# 24V_Sheet.net
KiCad netlist of a schematic drawn in Altium Designer
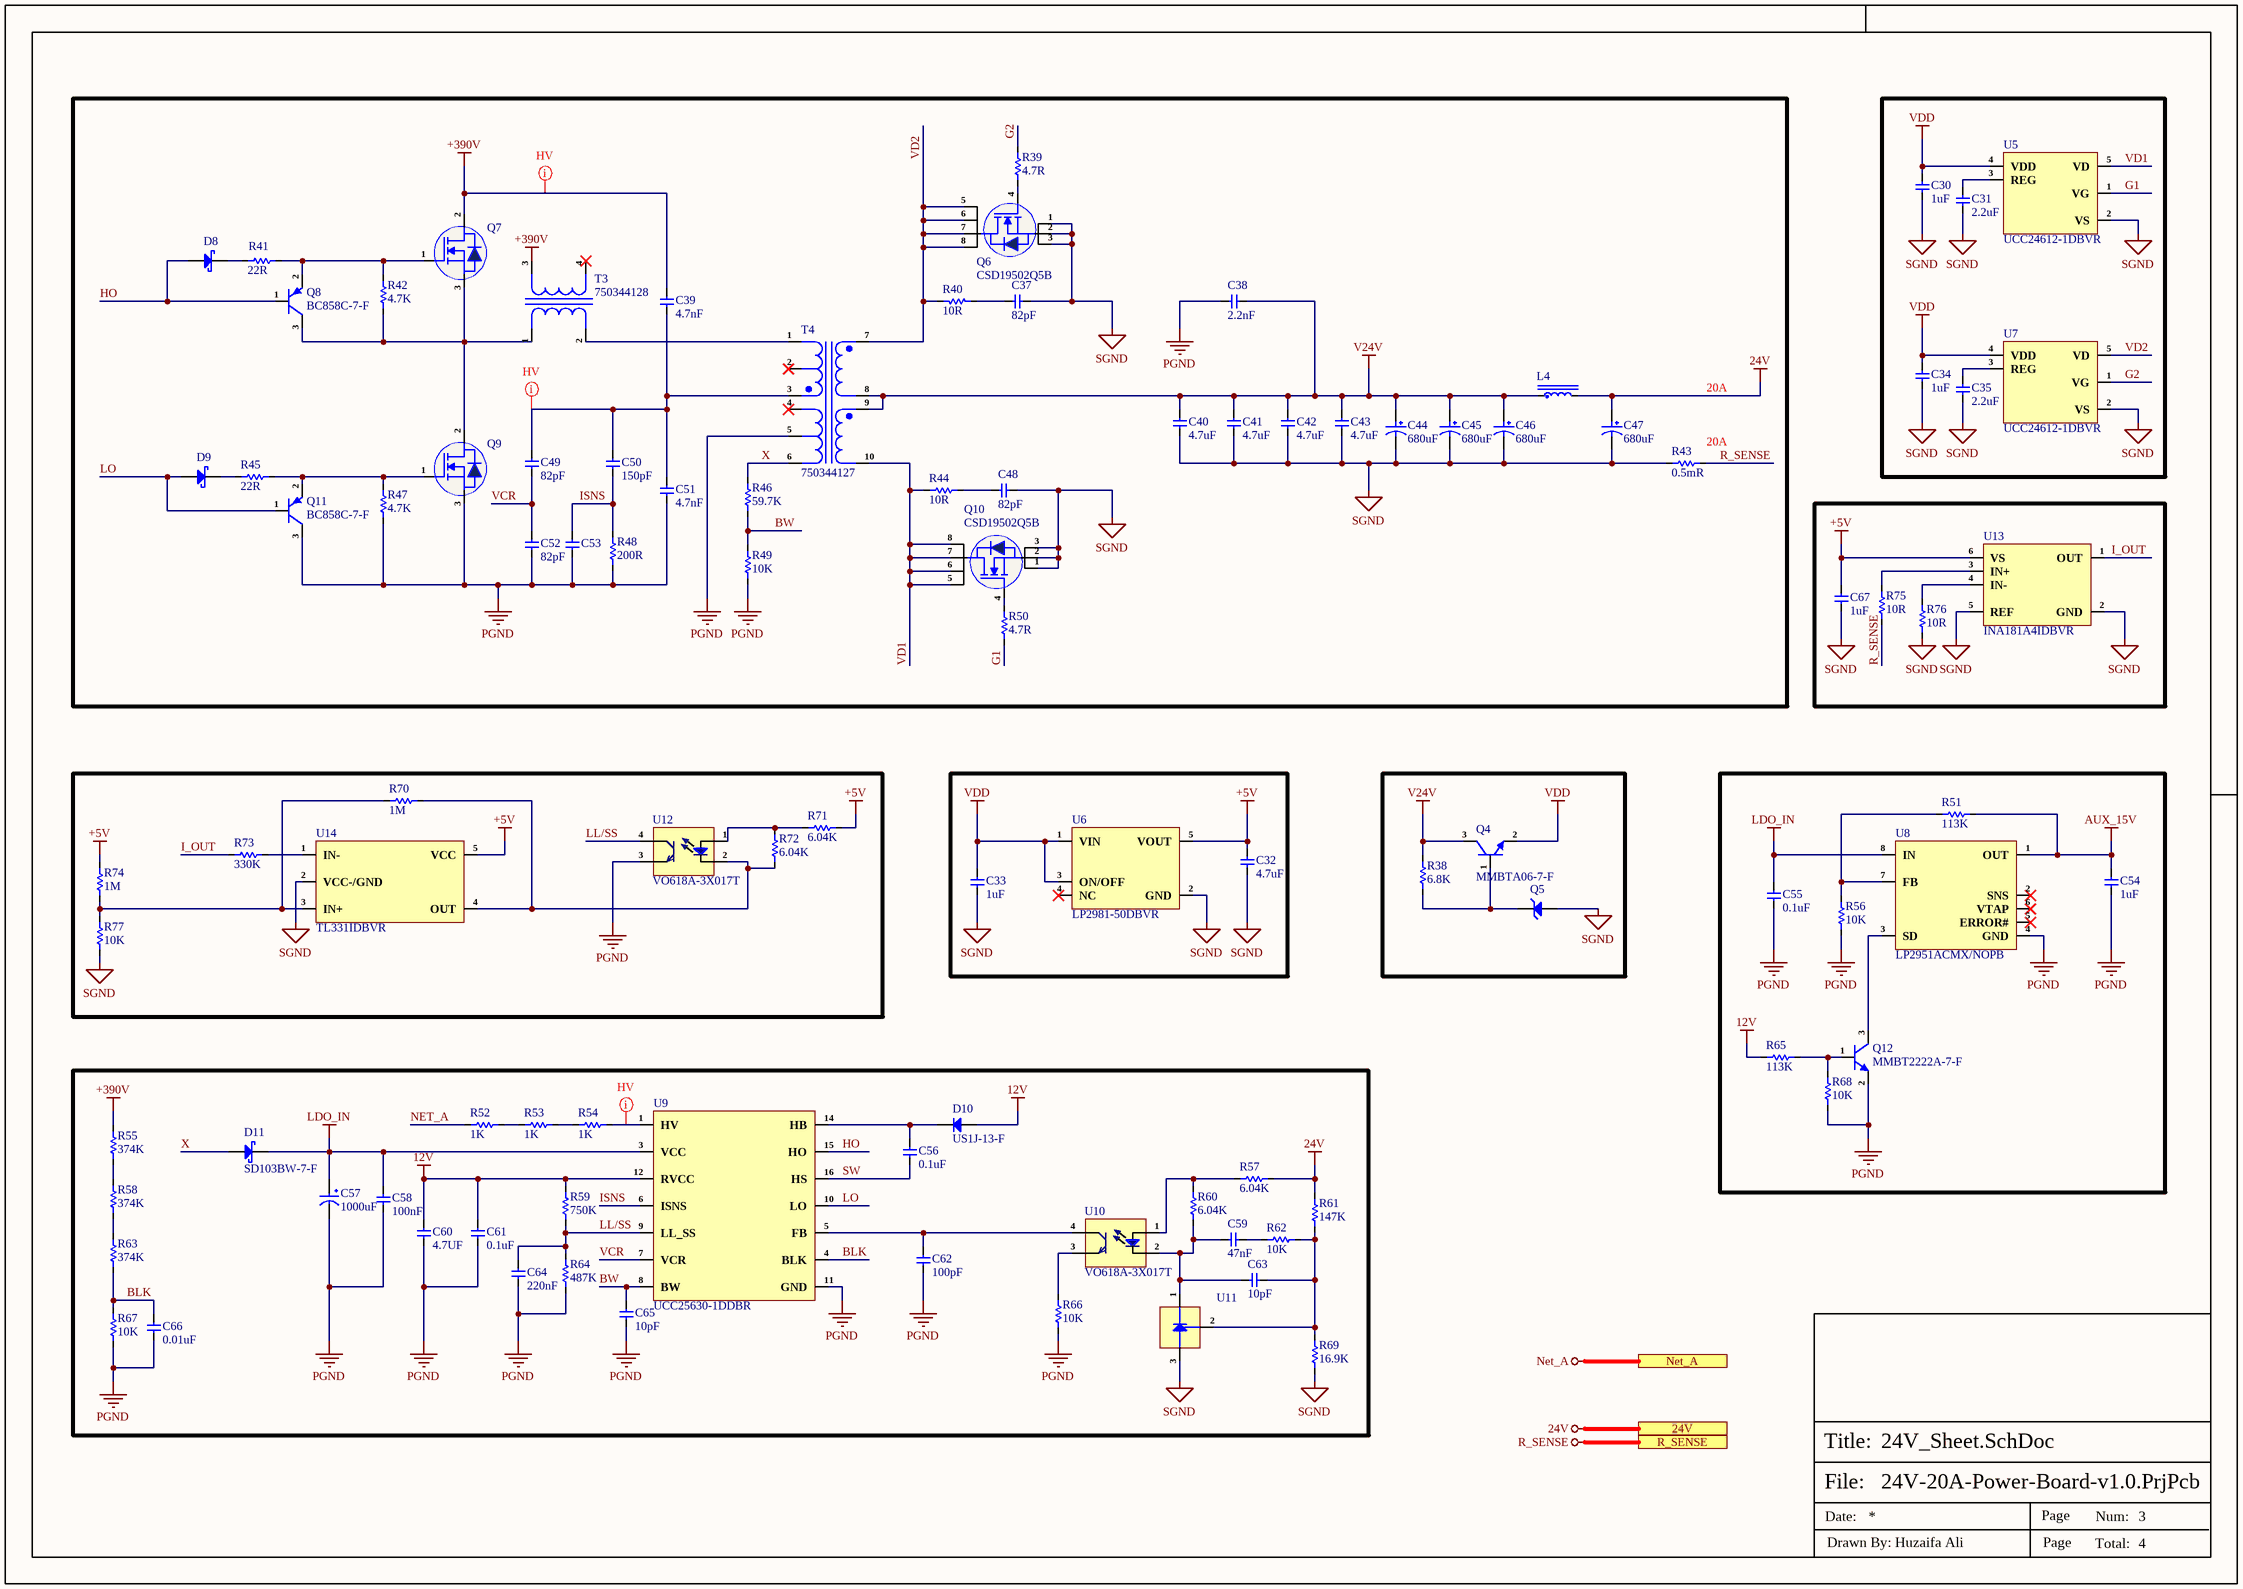
[diagram p0: 24V_Sheet.SchDoc]

(export (version "E")
  (design (tool "Eeschema 10.0.6"))
  (components
    (comp (ref "C30")
      (value "1uF")
      (footprint "Cap-0603")
      (description "1uF 25V X5R ±20% 0603 Multilayer Ceramic Capacitors MLCC - SMD/SMT ROHS")
      (fields (field (name "MANUFACTURER") "CCTC") (field (name "LCSC PART NUMBER") "C6266891"))
      (libsource (lib "eSpark Libraries") (part "TCC0603X5R105M250CT"))
    )
    (comp (ref "C31")
      (value "2.2uF")
      (footprint "Cap-0603")
      (description "CAP, 2.2µF, 35V, 10%, X5R, 0603")
      (fields
        (field (name "MANUFACTURER") "Murata")
        (field (name "MANUFACTURER PART NUMBER") "GRM188R6YA225KA12D")
      )
      (libsource (lib "eSpark Libraries") (part "GRM188R6YA225KA12D"))
    )
    (comp (ref "C32")
      (value "4.7uF")
      (footprint "Cap-0603")
      (description "CAP CER 4.7UF 16V X5R 0603")
      (fields
        (field (name "MANUFACTURER") "Yageo")
        (field (name "MANUFACTURER PART NUMBER") "CC0603KRX5R7BB475")
      )
      (libsource (lib "eSpark Libraries") (part "CC0603KRX5R7BB475"))
    )
    (comp (ref "C33")
      (value "1uF")
      (footprint "Cap-0603")
      (description "1uF 25V X5R ±20% 0603 Multilayer Ceramic Capacitors MLCC - SMD/SMT ROHS")
      (fields (field (name "MANUFACTURER") "CCTC") (field (name "LCSC PART NUMBER") "C6266891"))
      (libsource (lib "eSpark Libraries") (part "TCC0603X5R105M250CT"))
    )
    (comp (ref "C34")
      (value "1uF")
      (footprint "Cap-0603")
      (description "1uF 25V X5R ±20% 0603 Multilayer Ceramic Capacitors MLCC - SMD/SMT ROHS")
      (fields (field (name "MANUFACTURER") "CCTC") (field (name "LCSC PART NUMBER") "C6266891"))
      (libsource (lib "eSpark Libraries") (part "TCC0603X5R105M250CT"))
    )
    (comp (ref "C35")
      (value "2.2uF")
      (footprint "Cap-0603")
      (description "CAP, 2.2µF, 35V, 10%, X5R, 0603")
      (fields
        (field (name "MANUFACTURER") "Murata")
        (field (name "MANUFACTURER PART NUMBER") "GRM188R6YA225KA12D")
      )
      (libsource (lib "eSpark Libraries") (part "GRM188R6YA225KA12D"))
    )
    (comp (ref "C37")
      (value "82pF")
      (footprint "Cap-1206")
      (description "CAP CER 82PF 1KV U2J 1206")
      (fields (field (name "LCSC PART NUMBER") "C5125804") (field (name "MANUFACTURER") "Murata"))
      (libsource (lib "eSpark Libraries") (part "GCM31A7U3A820JX01D"))
    )
    (comp (ref "C38")
      (value "2.2nF")
      (footprint "KJKF222M2FF7035A075E")
      (description "2.2nF ±20% Y2 300V Plugin,P=7.5mm Safety Capacitors ROHS")
      (fields (field (name "LCSC PART NUMBER") "C2803195") (field (name "MANUFACTURER") "KNSCHA"))
      (libsource (lib "eSpark Libraries") (part "KJKF222M2FF7035A075E"))
    )
    (comp (ref "C39")
      (value "4.7nF")
      (footprint "MMK472J3AC2KN206G0")
      (description "4.7nF -40℃~+105℃ ±5% 1kV Plugin,P=10mm Polypropylene Film Capacitors (CBB) ROHS")
      (fields
        (field (name "MANUFACTURER") "KNSCHA")
        (field (name "MANUFACTURER PART NUMBER") "MMK472J3AC2KN206G0")
      )
      (libsource (lib "eSpark Libraries") (part "MMK472J3AC2KN206G0"))
    )
    (comp (ref "C40")
      (value "4.7uF")
      (footprint "Cap-1206")
      (description "CAP CER 4.7UF 100V X7S 1206")
      (fields
        (field (name "MANUFACTURER") "Murata")
        (field (name "MANUFACTURER PART NUMBER") "GRM31CC72A475KE11L")
      )
      (libsource (lib "eSpark Libraries") (part "GRM31CC72A475KE11L"))
    )
    (comp (ref "C41")
      (value "4.7uF")
      (footprint "Cap-1206")
      (description "CAP CER 4.7UF 100V X7S 1206")
      (fields
        (field (name "MANUFACTURER") "Murata")
        (field (name "MANUFACTURER PART NUMBER") "GRM31CC72A475KE11L")
      )
      (libsource (lib "eSpark Libraries") (part "GRM31CC72A475KE11L"))
    )
    (comp (ref "C42")
      (value "4.7uF")
      (footprint "Cap-1206")
      (description "CAP CER 4.7UF 100V X7S 1206")
      (fields
        (field (name "MANUFACTURER") "Murata")
        (field (name "MANUFACTURER PART NUMBER") "GRM31CC72A475KE11L")
      )
      (libsource (lib "eSpark Libraries") (part "GRM31CC72A475KE11L"))
    )
    (comp (ref "C43")
      (value "4.7uF")
      (footprint "Cap-1206")
      (description "CAP CER 4.7UF 100V X7S 1206")
      (fields
        (field (name "MANUFACTURER") "Murata")
        (field (name "MANUFACTURER PART NUMBER") "GRM31CC72A475KE11L")
      )
      (libsource (lib "eSpark Libraries") (part "GRM31CC72A475KE11L"))
    )
    (comp (ref "C44")
      (value "680uF")
      (footprint "ERS1HM681W20OT")
      (description "680uF 50V ±20% Plugin,D12.5xL20mm Aluminum Electrolytic Capacitors - Leaded ROHS")
      (fields
        (field (name "MANUFACTURER") "AISHI")
        (field (name "MANUFACTURER PART NUMBER") "ERS1HM681W20OT")
      )
      (libsource (lib "eSpark Libraries") (part "ERS1HM681W20OT"))
    )
    (comp (ref "C45")
      (value "680uF")
      (footprint "ERS1HM681W20OT")
      (description "680uF 50V ±20% Plugin,D12.5xL20mm Aluminum Electrolytic Capacitors - Leaded ROHS")
      (fields
        (field (name "MANUFACTURER") "AISHI")
        (field (name "MANUFACTURER PART NUMBER") "ERS1HM681W20OT")
      )
      (libsource (lib "eSpark Libraries") (part "ERS1HM681W20OT"))
    )
    (comp (ref "C46")
      (value "680uF")
      (footprint "ERS1HM681W20OT")
      (description "680uF 50V ±20% Plugin,D12.5xL20mm Aluminum Electrolytic Capacitors - Leaded ROHS")
      (fields
        (field (name "MANUFACTURER") "AISHI")
        (field (name "MANUFACTURER PART NUMBER") "ERS1HM681W20OT")
      )
      (libsource (lib "eSpark Libraries") (part "ERS1HM681W20OT"))
    )
    (comp (ref "C47")
      (value "680uF")
      (footprint "ERS1HM681W20OT")
      (description "680uF 50V ±20% Plugin,D12.5xL20mm Aluminum Electrolytic Capacitors - Leaded ROHS")
      (fields
        (field (name "MANUFACTURER") "AISHI")
        (field (name "MANUFACTURER PART NUMBER") "ERS1HM681W20OT")
      )
      (libsource (lib "eSpark Libraries") (part "ERS1HM681W20OT"))
    )
    (comp (ref "C48")
      (value "82pF")
      (footprint "Cap-1206")
      (description "CAP CER 82PF 1KV U2J 1206")
      (fields (field (name "LCSC PART NUMBER") "C5125804") (field (name "MANUFACTURER") "Murata"))
      (libsource (lib "eSpark Libraries") (part "GCM31A7U3A820JX01D"))
    )
    (comp (ref "C49")
      (value "82pF")
      (footprint "Cap-1206")
      (description "CAP CER 82PF 1KV U2J 1206")
      (fields (field (name "LCSC PART NUMBER") "C5125804") (field (name "MANUFACTURER") "Murata"))
      (libsource (lib "eSpark Libraries") (part "GCM31A7U3A820JX01D"))
    )
    (comp (ref "C50")
      (value "150pF")
      (footprint "Cap-1206")
      (description "CAP CER 150PF 1KV U2J 1206")
      (fields (field (name "LCSC PART NUMBER") "C162467") (field (name "MANUFACTURER") "Murata"))
      (libsource (lib "eSpark Libraries") (part "GRM31A7U3A151JW31D"))
    )
    (comp (ref "C51")
      (value "4.7nF")
      (footprint "MMK472J3AC2KN206G0")
      (description "4.7nF -40℃~+105℃ ±5% 1kV Plugin,P=10mm Polypropylene Film Capacitors (CBB) ROHS")
      (fields
        (field (name "MANUFACTURER") "KNSCHA")
        (field (name "MANUFACTURER PART NUMBER") "MMK472J3AC2KN206G0")
      )
      (libsource (lib "eSpark Libraries") (part "MMK472J3AC2KN206G0"))
    )
    (comp (ref "C52")
      (value "82pF")
      (footprint "Cap-1206")
      (description "CAP CER 82PF 1KV U2J 1206")
      (fields (field (name "LCSC PART NUMBER") "C5125804") (field (name "MANUFACTURER") "Murata"))
      (libsource (lib "eSpark Libraries") (part "GCM31A7U3A820JX01D"))
    )
    (comp (ref "C53")
      (value "RF15N3R3C500CT")
      (footprint "Cap-0402")
      (description "CAP CER 3.3PF 50V C0G/NP0 0402")
      (fields (field (name "MANUFACTURER") "Walsin Tech Corp") (field (name "LCSC PART NUMBER") "C172822"))
      (libsource (lib "eSpark Libraries") (part "RF15N3R3C500CT"))
    )
    (comp (ref "C54")
      (value "1uF")
      (footprint "Cap-0603")
      (description "1uF 25V X5R ±20% 0603 Multilayer Ceramic Capacitors MLCC - SMD/SMT ROHS")
      (fields (field (name "MANUFACTURER") "CCTC") (field (name "LCSC PART NUMBER") "C6266891"))
      (libsource (lib "eSpark Libraries") (part "TCC0603X5R105M250CT"))
    )
    (comp (ref "C55")
      (value "0.1uF")
      (footprint "Cap-1206")
      (description "50V 100nF C0G ±1% 1206 Multilayer Ceramic Capacitors MLCC - SMD/SMT ROHS")
      (fields (field (name "LCSC PART NUMBER") "C2981728") (field (name "MANUFACTURER") "Murata Electronics"))
      (libsource (lib "eSpark Libraries") (part "GRM31C5C1H104FA01L"))
    )
    (comp (ref "C56")
      (value "0.1uF")
      (footprint "Cap-0805")
      (description "CAP CER 0.1UF 100V X7R 0805")
      (fields (field (name "LCSC PART NUMBER") "C106243") (field (name "MANUFACTURER") "Yageo"))
      (libsource (lib "eSpark Libraries") (part "CC0805KKX7R0BB104"))
    )
    (comp (ref "C57")
      (value "1000uF")
      (footprint "VZH102M1HTR-1616")
      (description "1000uF 50V ±20% SMD,D16xL16.5mm Aluminum Electrolytic Capacitors - SMD ROHS")
      (fields (field (name "LCSC PART NUMBER") "C5266058") (field (name "MANUFACTURER") "Surge Components"))
      (libsource (lib "eSpark Libraries") (part "VZH102M1HTR-1616CS"))
    )
    (comp (ref "C58")
      (value "100nF")
      (footprint "Cap-0603")
      (description "CAP CER 0.1UF 50V X5R 0603")
      (fields
        (field (name "MANUFACTURER") "Yageo")
        (field (name "MANUFACTURER PART NUMBER") "CC0603KRX5R9BB104")
      )
      (libsource (lib "eSpark Libraries") (part "CC0603KRX5R9BB104"))
    )
    (comp (ref "C59")
      (value "47nF")
      (footprint "Cap-0402")
      (description "CAP CER 0.047UF 25V X7R 0402")
      (fields
        (field (name "MANUFACTURER") "Murata")
        (field (name "MANUFACTURER PART NUMBER") "GRM155R71E473KA88D")
      )
      (libsource (lib "eSpark Libraries") (part "GRM155R71E473KA88D"))
    )
    (comp (ref "C60")
      (value "4.7UF")
      (footprint "Cap-0603")
      (description "CAP CER 4.7UF 25V X5R 0603")
      (fields
        (field (name "MANUFACTURER") "Samsung")
        (field (name "MANUFACTURER PART NUMBER") "CL10A475KA8NQNC")
      )
      (libsource (lib "eSpark Libraries") (part "CL10A475KA8NQNC"))
    )
    (comp (ref "C61")
      (value "0.1uF")
      (footprint "Cap-0805")
      (description "CAP CER 0.1UF 100V X7R 0805")
      (fields (field (name "LCSC PART NUMBER") "C106243") (field (name "MANUFACTURER") "Yageo"))
      (libsource (lib "eSpark Libraries") (part "CC0805KKX7R0BB104"))
    )
    (comp (ref "C62")
      (value "100pF")
      (footprint "Cap-0603")
      (description "CAP CER 100PF 50V C0G/NPO 0603")
      (fields
        (field (name "MANUFACTURER") "Yageo")
        (field (name "MANUFACTURER PART NUMBER") "CC0603JRNPO9BN101")
      )
      (libsource (lib "eSpark Libraries") (part "CC0603JRNPO9BN101"))
    )
    (comp (ref "C63")
      (value "10pF")
      (footprint "Cap-0603")
      (description "CAP CER 10PF 50V C0G/NPO 0603")
      (fields
        (field (name "MANUFACTURER") "Yageo")
        (field (name "MANUFACTURER PART NUMBER") "CC0603JRNPO9BN100")
      )
      (libsource (lib "eSpark Libraries") (part "CC0603JRNPO9BN100"))
    )
    (comp (ref "C64")
      (value "220nF")
      (footprint "Cap-1206")
      (description "CAP CER 0.22UF 50V X7R 1206")
      (fields
        (field (name "MANUFACTURER") "Yageo")
        (field (name "MANUFACTURER PART NUMBER") "CC1206JKX7R9BB224")
      )
      (libsource (lib "eSpark Libraries") (part "CC1206JKX7R9BB224"))
    )
    (comp (ref "C65")
      (value "10pF")
      (footprint "Cap-0603")
      (description "CAP CER 10PF 50V C0G/NPO 0603")
      (fields
        (field (name "MANUFACTURER") "Yageo")
        (field (name "MANUFACTURER PART NUMBER") "CC0603JRNPO9BN100")
      )
      (libsource (lib "eSpark Libraries") (part "CC0603JRNPO9BN100"))
    )
    (comp (ref "C66")
      (value "0.01uF")
      (footprint "Cap-0805")
      (description "Multilayer Ceramic Capacitor, 0.01 uF, 50 V, ± 10%, X7R, 0805 [2012 Metric]")
      (fields
        (field (name "MANUFACTURER") "Yageo")
        (field (name "MANUFACTURER PART NUMBER") "CC0805KRX7R9BB103")
      )
      (libsource (lib "eSpark Libraries") (part "CC0805KRX7R9BB103"))
    )
    (comp (ref "C67")
      (value "1uF")
      (footprint "Cap-0603")
      (description "1uF 25V X5R ±20% 0603 Multilayer Ceramic Capacitors MLCC - SMD/SMT ROHS")
      (fields (field (name "MANUFACTURER") "CCTC") (field (name "LCSC PART NUMBER") "C6266891"))
      (libsource (lib "eSpark Libraries") (part "TCC0603X5R105M250CT"))
    )
    (comp (ref "D8")
      (value "SD103BW-7-F")
      (footprint "SOD-123")
      (description "DIODE SCHOTTKY 30V 350MA SOD123")
      (fields (field (name "LCSC PART NUMBER") "C151400") (field (name "MANUFACTURER") "Diodes"))
      (libsource (lib "eSpark Libraries") (part "SD103BW-7-F"))
    )
    (comp (ref "D9")
      (value "SD103BW-7-F")
      (footprint "SOD-123")
      (description "DIODE SCHOTTKY 30V 350MA SOD123")
      (fields (field (name "LCSC PART NUMBER") "C151400") (field (name "MANUFACTURER") "Diodes"))
      (libsource (lib "eSpark Libraries") (part "SD103BW-7-F"))
    )
    (comp (ref "D10")
      (value "US1J-13-F")
      (footprint "SMA")
      (description "DIODE GEN PURP 600V 1A SMA")
      (fields (field (name "LCSC PART NUMBER") "C85095") (field (name "MANUFACTURER") "Diodes"))
      (libsource (lib "eSpark Libraries") (part "US1J-13-F"))
    )
    (comp (ref "D11")
      (value "SD103BW-7-F")
      (footprint "SOD-123")
      (description "DIODE SCHOTTKY 30V 350MA SOD123")
      (fields (field (name "LCSC PART NUMBER") "C151400") (field (name "MANUFACTURER") "Diodes"))
      (libsource (lib "eSpark Libraries") (part "SD103BW-7-F"))
    )
    (comp (ref "L4")
      (value "PA2607.301NLT")
      (footprint "PA2607.301NLT")
      (description "FIXED IND 300NH 27A 0.29MOHM SMD")
      (fields (field (name "MANUFACTURER") "Pulse"))
      (libsource (lib "eSpark Libraries") (part "PA2607.301NLT"))
    )
    (comp (ref "Q4")
      (value "MMBTA06-7-F")
      (footprint "SOT-23")
      (description "TRANS NPN 80V 0.5A SOT23-3")
      (fields (field (name "MANUFACTURER") "Diodes"))
      (libsource (lib "eSpark Libraries") (part "MMBTA06-7-F"))
    )
    (comp (ref "Q5")
      (value "BZX384-C15,115")
      (footprint "SOD-323")
      (description "DIODE ZENER 15V 300MW SOD323")
      (fields (field (name "LCSC PART NUMBER") "C454989") (field (name "MANUFACTURER") "Nexperia"))
      (libsource (lib "eSpark Libraries") (part "BZX384-C15,115"))
    )
    (comp (ref "Q6")
      (value "CSD19502Q5B")
      (footprint "8-VSONP (5x6)")
      (description "MOSFET N-CH 80V 100A 8VSON")
      (fields (field (name "MANUFACTURER") "Texas Instruments") (field (name "LCSC PART NUMBER") "C2864118"))
      (libsource (lib "eSpark Libraries") (part "CSD19502Q5B"))
    )
    (comp (ref "Q7")
      (value "IPA60R120P7XKSA1")
      (footprint "TO-220-3")
      (description "MOSFET N-CH 600V 26A TO220")
      (fields (field (name "MANUFACTURER") "Infineon"))
      (libsource (lib "eSpark Libraries") (part "IPA60R120P7XKSA1"))
    )
    (comp (ref "Q8")
      (value "BC858C-7-F")
      (footprint "SOT-23")
      (description "TRANS PNP 30V 0.1A SOT23-3")
      (fields (field (name "LCSC PART NUMBER") "C526469") (field (name "MANUFACTURER") "Diodes"))
      (libsource (lib "eSpark Libraries") (part "BC858C-7-F"))
    )
    (comp (ref "Q9")
      (value "IPA60R120P7XKSA1")
      (footprint "TO-220-3")
      (description "MOSFET N-CH 600V 26A TO220")
      (fields (field (name "MANUFACTURER") "Infineon"))
      (libsource (lib "eSpark Libraries") (part "IPA60R120P7XKSA1"))
    )
    (comp (ref "Q10")
      (value "CSD19502Q5B")
      (footprint "8-VSONP (5x6)")
      (description "MOSFET N-CH 80V 100A 8VSON")
      (fields (field (name "MANUFACTURER") "Texas Instruments") (field (name "LCSC PART NUMBER") "C2864118"))
      (libsource (lib "eSpark Libraries") (part "CSD19502Q5B"))
    )
    (comp (ref "Q11")
      (value "BC858C-7-F")
      (footprint "SOT-23")
      (description "TRANS PNP 30V 0.1A SOT23-3")
      (fields (field (name "LCSC PART NUMBER") "C526469") (field (name "MANUFACTURER") "Diodes"))
      (libsource (lib "eSpark Libraries") (part "BC858C-7-F"))
    )
    (comp (ref "Q12")
      (value "MMBT2222A-7-F")
      (footprint "SOT-23")
      (description "TRANS NPN 40V 0.6A SMD SOT23-3")
      (fields (field (name "MANUFACTURER") "Diodes") (field (name "VOLTAGE") "40V"))
      (libsource (lib "eSpark Libraries") (part "MMBT2222A-7-F"))
    )
    (comp (ref "R38")
      (value "6.8K")
      (footprint "Res-0603")
      (description "RES SMD 6.8K OHM 0.1% 1/10W 0603")
      (fields
        (field (name "MANUFACTURER") "Yageo")
        (field (name "MANUFACTURER PART NUMBER") "RT0603BRE076K8L")
      )
      (libsource (lib "eSpark Libraries") (part "RT0603BRE076K8L"))
    )
    (comp (ref "R39")
      (value "4.7R")
      (footprint "Res-0603")
      (description "RES 4.7 OHM 1% 1/10W 0603")
      (fields
        (field (name "MANUFACTURER") "Yageo")
        (field (name "MANUFACTURER PART NUMBER") "RC0603FR-074R7L")
      )
      (libsource (lib "eSpark Libraries") (part "RC0603FR-074R7L"))
    )
    (comp (ref "R40")
      (value "10R")
      (footprint "RES-0805")
      (description "RES SMD 10 OHM 1% 1/2W 0805")
      (fields (field (name "LCSC PART NUMBER") "C844598") (field (name "MANUFACTURER") "Vishay"))
      (libsource (lib "eSpark Libraries") (part "CRCW080510R0FKEAHP"))
    )
    (comp (ref "R41")
      (value "22R")
      (footprint "Res-0603")
      (description "RES 22 OHM 1% 1/10W 0603")
      (fields
        (field (name "MANUFACTURER") "Yageo")
        (field (name "MANUFACTURER PART NUMBER") "RC0603FR-0722RL")
      )
      (libsource (lib "eSpark Libraries") (part "RC0603FR-0722RL"))
    )
    (comp (ref "R42")
      (value "4.7K")
      (footprint "Res-0603")
      (description "RES SMD 4.7K OHM 1% 1/10W 0603")
      (fields
        (field (name "MANUFACTURER") "Yageo")
        (field (name "MANUFACTURER PART NUMBER") "RC0603FR-074K7L")
      )
      (libsource (lib "eSpark Libraries") (part "RC0603FR-074K7L"))
    )
    (comp (ref "R43")
      (value "0.5mR")
      (footprint "RES-2512")
      (description "METAL CURRENT SENSOR 2512 1% 100")
      (fields (field (name "LCSC PART NUMBER") "PA2512FKF7T0U5E") (field (name "MANUFACTURER") "Yageo"))
      (libsource (lib "eSpark Libraries") (part "PA2512FKF7T0U5E"))
    )
    (comp (ref "R44")
      (value "10R")
      (footprint "RES-0805")
      (description "RES SMD 10 OHM 1% 1/2W 0805")
      (fields (field (name "LCSC PART NUMBER") "C844598") (field (name "MANUFACTURER") "Vishay"))
      (libsource (lib "eSpark Libraries") (part "CRCW080510R0FKEAHP"))
    )
    (comp (ref "R45")
      (value "22R")
      (footprint "Res-0603")
      (description "RES 22 OHM 1% 1/10W 0603")
      (fields
        (field (name "MANUFACTURER") "Yageo")
        (field (name "MANUFACTURER PART NUMBER") "RC0603FR-0722RL")
      )
      (libsource (lib "eSpark Libraries") (part "RC0603FR-0722RL"))
    )
    (comp (ref "R46")
      (value "59.7K")
      (footprint "Res-0603")
      (description "RES SMD 59.7KOHM 0.1% 1/10W 0603")
      (fields (field (name "LCSC PART NUMBER") "C861481") (field (name "MANUFACTURER") "Yageo"))
      (libsource (lib "eSpark Libraries") (part "RT0603BRD0759K7L"))
    )
    (comp (ref "R47")
      (value "4.7K")
      (footprint "Res-0603")
      (description "RES SMD 4.7K OHM 1% 1/10W 0603")
      (fields
        (field (name "MANUFACTURER") "Yageo")
        (field (name "MANUFACTURER PART NUMBER") "RC0603FR-074K7L")
      )
      (libsource (lib "eSpark Libraries") (part "RC0603FR-074K7L"))
    )
    (comp (ref "R48")
      (value "200R")
      (footprint "RES-0805")
      (description "RES 200 OHM 1% 1/8W 0805")
      (fields
        (field (name "MANUFACTURER") "Yageo")
        (field (name "MANUFACTURER PART NUMBER") "RC0805FR-07200RL")
      )
      (libsource (lib "eSpark Libraries") (part "RC0805FR-07200RL"))
    )
    (comp (ref "R49")
      (value "10K")
      (footprint "Res-0603")
      (description "RES SMD 10K Ohm 1% 1/10W 0603")
      (fields
        (field (name "MANUFACTURER") "Yageo")
        (field (name "MANUFACTURER PART NUMBER") "RC0603FR-0710KL")
      )
      (libsource (lib "eSpark Libraries") (part "RC0603FR-0710KL"))
    )
    (comp (ref "R50")
      (value "4.7R")
      (footprint "Res-0603")
      (description "RES 4.7 OHM 1% 1/10W 0603")
      (fields
        (field (name "MANUFACTURER") "Yageo")
        (field (name "MANUFACTURER PART NUMBER") "RC0603FR-074R7L")
      )
      (libsource (lib "eSpark Libraries") (part "RC0603FR-074R7L"))
    )
    (comp (ref "R51")
      (value "113K")
      (footprint "Res-0603")
      (description "RES 113K OHM 1% 1/10W 0603")
      (fields
        (field (name "MANUFACTURER") "Yageo")
        (field (name "MANUFACTURER PART NUMBER") "RC0603FR-07113KL")
      )
      (libsource (lib "eSpark Libraries") (part "RC0603FR-07113KL"))
    )
    (comp (ref "R52")
      (value "1K")
      (footprint "Res-1206")
      (description "RES 1K OHM 1% 1/2W 1206")
      (fields
        (field (name "MANUFACTURER") "Yageo")
        (field (name "MANUFACTURER PART NUMBER") "RC1206FR-7W1KL")
      )
      (libsource (lib "eSpark Libraries") (part "RC1206FR-7W1KL"))
    )
    (comp (ref "R53")
      (value "1K")
      (footprint "Res-1206")
      (description "RES 1K OHM 1% 1/2W 1206")
      (fields
        (field (name "MANUFACTURER") "Yageo")
        (field (name "MANUFACTURER PART NUMBER") "RC1206FR-7W1KL")
      )
      (libsource (lib "eSpark Libraries") (part "RC1206FR-7W1KL"))
    )
    (comp (ref "R54")
      (value "1K")
      (footprint "Res-1206")
      (description "RES 1K OHM 1% 1/2W 1206")
      (fields
        (field (name "MANUFACTURER") "Yageo")
        (field (name "MANUFACTURER PART NUMBER") "RC1206FR-7W1KL")
      )
      (libsource (lib "eSpark Libraries") (part "RC1206FR-7W1KL"))
    )
    (comp (ref "R55")
      (value "374K")
      (footprint "Res-1206")
      (description "RES SMD 374K OHM 0.5% 1/4W 1206")
      (fields
        (field (name "LCSC PART NUMBER") "C346652")
        (field (name "MANUFACTURER") "Stackpole Electronics")
      )
      (libsource (lib "eSpark Libraries") (part "RNCF1206DTE374K"))
    )
    (comp (ref "R56")
      (value "10K")
      (footprint "Res-0603")
      (description "RES SMD 10K Ohm 1% 1/10W 0603")
      (fields
        (field (name "MANUFACTURER") "Yageo")
        (field (name "MANUFACTURER PART NUMBER") "RC0603FR-0710KL")
      )
      (libsource (lib "eSpark Libraries") (part "RC0603FR-0710KL"))
    )
    (comp (ref "R57")
      (value "6.04K")
      (footprint "Res-0402")
      (description "RES 6.04K OHM 1% 1/16W 0402")
      (fields
        (field (name "MANUFACTURER") "Yageo")
        (field (name "MANUFACTURER PART NUMBER") "RC0402FR-076K04L")
      )
      (libsource (lib "eSpark Libraries") (part "RC0402FR-076K04L"))
    )
    (comp (ref "R58")
      (value "374K")
      (footprint "Res-1206")
      (description "RES SMD 374K OHM 0.5% 1/4W 1206")
      (fields
        (field (name "LCSC PART NUMBER") "C346652")
        (field (name "MANUFACTURER") "Stackpole Electronics")
      )
      (libsource (lib "eSpark Libraries") (part "RNCF1206DTE374K"))
    )
    (comp (ref "R59")
      (value "750K")
      (footprint "Res-0603")
      (description "100mW Thick Film Resistors 75V ±100ppm/℃ ±1% 750kΩ 0603 Chip Resistor - Surface Mount ROHS")
      (fields
        (field (name "MANUFACTURER") "UNI-ROYAL")
        (field (name "MANUFACTURER PART NUMBER") "0603WAF7503T5E")
      )
      (libsource (lib "eSpark Libraries") (part "0603WAF7503T5E"))
    )
    (comp (ref "R60")
      (value "6.04K")
      (footprint "Res-0402")
      (description "RES 6.04K OHM 1% 1/16W 0402")
      (fields
        (field (name "MANUFACTURER") "Yageo")
        (field (name "MANUFACTURER PART NUMBER") "RC0402FR-076K04L")
      )
      (libsource (lib "eSpark Libraries") (part "RC0402FR-076K04L"))
    )
    (comp (ref "R61")
      (value "147K")
      (footprint "Res-0603")
      (description "RES SMD 147K OHM 0.5% 1/10W 0603")
      (fields
        (field (name "MANUFACTURER") "Yageo")
        (field (name "MANUFACTURER PART NUMBER") "RT0603DRD07147KL")
      )
      (libsource (lib "eSpark Libraries") (part "RT0603DRD07147KL"))
    )
    (comp (ref "R62")
      (value "10K")
      (footprint "Res-0603")
      (description "RES SMD 10K Ohm 1% 1/10W 0603")
      (fields
        (field (name "MANUFACTURER") "Yageo")
        (field (name "MANUFACTURER PART NUMBER") "RC0603FR-0710KL")
      )
      (libsource (lib "eSpark Libraries") (part "RC0603FR-0710KL"))
    )
    (comp (ref "R63")
      (value "374K")
      (footprint "Res-1206")
      (description "RES SMD 374K OHM 0.5% 1/4W 1206")
      (fields
        (field (name "LCSC PART NUMBER") "C346652")
        (field (name "MANUFACTURER") "Stackpole Electronics")
      )
      (libsource (lib "eSpark Libraries") (part "RNCF1206DTE374K"))
    )
    (comp (ref "R64")
      (value "487K")
      (footprint "Res-0603")
      (description "RES 487K OHM 0.5% 1/10W 0603")
      (fields (field (name "LCSC PART NUMBER") "C859043") (field (name "MANUFACTURER") "Yageo"))
      (libsource (lib "eSpark Libraries") (part "RC0603DR-07487KL"))
    )
    (comp (ref "R65")
      (value "113K")
      (footprint "Res-0603")
      (description "RES 113K OHM 1% 1/10W 0603")
      (fields
        (field (name "MANUFACTURER") "Yageo")
        (field (name "MANUFACTURER PART NUMBER") "RC0603FR-07113KL")
      )
      (libsource (lib "eSpark Libraries") (part "RC0603FR-07113KL"))
    )
    (comp (ref "R66")
      (value "10K")
      (footprint "Res-0603")
      (description "RES SMD 10K Ohm 1% 1/10W 0603")
      (fields
        (field (name "MANUFACTURER") "Yageo")
        (field (name "MANUFACTURER PART NUMBER") "RC0603FR-0710KL")
      )
      (libsource (lib "eSpark Libraries") (part "RC0603FR-0710KL"))
    )
    (comp (ref "R67")
      (value "10K")
      (footprint "Res-0603")
      (description "RES SMD 10K Ohm 1% 1/10W 0603")
      (fields
        (field (name "MANUFACTURER") "Yageo")
        (field (name "MANUFACTURER PART NUMBER") "RC0603FR-0710KL")
      )
      (libsource (lib "eSpark Libraries") (part "RC0603FR-0710KL"))
    )
    (comp (ref "R68")
      (value "10K")
      (footprint "Res-0603")
      (description "RES SMD 10K Ohm 1% 1/10W 0603")
      (fields
        (field (name "MANUFACTURER") "Yageo")
        (field (name "MANUFACTURER PART NUMBER") "RC0603FR-0710KL")
      )
      (libsource (lib "eSpark Libraries") (part "RC0603FR-0710KL"))
    )
    (comp (ref "R69")
      (value "16.9K")
      (footprint "Res-0603")
      (description "100mW Thick Film Resistors 75V ±100ppm/℃ ±1% 16.9kΩ 0603 Chip Resistor - Surface Mount ROHS")
      (fields
        (field (name "MANUFACTURER") "UNI-ROYAL")
        (field (name "MANUFACTURER PART NUMBER") "0603WAF1692T5E")
      )
      (libsource (lib "eSpark Libraries") (part "0603WAF1692T5E"))
    )
    (comp (ref "R70")
      (value "1M")
      (footprint "Res-0402")
      (description "RES 1M OHM 1% 1/16W 0402")
      (fields
        (field (name "MANUFACTURER") "Yageo")
        (field (name "MANUFACTURER PART NUMBER") "RC0402FR-071ML")
      )
      (libsource (lib "eSpark Libraries") (part "RC0402FR-071ML"))
    )
    (comp (ref "R71")
      (value "6.04K")
      (footprint "Res-0402")
      (description "RES 6.04K OHM 1% 1/16W 0402")
      (fields
        (field (name "MANUFACTURER") "Yageo")
        (field (name "MANUFACTURER PART NUMBER") "RC0402FR-076K04L")
      )
      (libsource (lib "eSpark Libraries") (part "RC0402FR-076K04L"))
    )
    (comp (ref "R72")
      (value "6.04K")
      (footprint "Res-0402")
      (description "RES 6.04K OHM 1% 1/16W 0402")
      (fields
        (field (name "MANUFACTURER") "Yageo")
        (field (name "MANUFACTURER PART NUMBER") "RC0402FR-076K04L")
      )
      (libsource (lib "eSpark Libraries") (part "RC0402FR-076K04L"))
    )
    (comp (ref "R73")
      (value "330K")
      (footprint "Res-0402")
      (description "RES 330K OHM 1% 1/16W 0402")
      (fields
        (field (name "MANUFACTURER") "Vishay")
        (field (name "MANUFACTURER PART NUMBER") "CRCW0402330KFKEDC")
      )
      (libsource (lib "eSpark Libraries") (part "CRCW0402330KFKEDC"))
    )
    (comp (ref "R74")
      (value "1M")
      (footprint "Res-0402")
      (description "RES 1M OHM 1% 1/16W 0402")
      (fields
        (field (name "MANUFACTURER") "Yageo")
        (field (name "MANUFACTURER PART NUMBER") "RC0402FR-071ML")
      )
      (libsource (lib "eSpark Libraries") (part "RC0402FR-071ML"))
    )
    (comp (ref "R75")
      (value "10R")
      (footprint "RES-0805")
      (description "RES SMD 10 OHM 1% 1/2W 0805")
      (fields (field (name "LCSC PART NUMBER") "C844598") (field (name "MANUFACTURER") "Vishay"))
      (libsource (lib "eSpark Libraries") (part "CRCW080510R0FKEAHP"))
    )
    (comp (ref "R76")
      (value "10R")
      (footprint "RES-0805")
      (description "RES SMD 10 OHM 1% 1/2W 0805")
      (fields (field (name "LCSC PART NUMBER") "C844598") (field (name "MANUFACTURER") "Vishay"))
      (libsource (lib "eSpark Libraries") (part "CRCW080510R0FKEAHP"))
    )
    (comp (ref "R77")
      (value "10K")
      (footprint "Res-0603")
      (description "RES SMD 10K Ohm 1% 1/10W 0603")
      (fields
        (field (name "MANUFACTURER") "Yageo")
        (field (name "MANUFACTURER PART NUMBER") "RC0603FR-0710KL")
      )
      (libsource (lib "eSpark Libraries") (part "RC0603FR-0710KL"))
    )
    (comp (ref "T3")
      (value "750344128")
      (fields (field (name "MANUFACTURER") "Wurth Electroniks"))
      (libsource (lib "eSpark Libraries") (part "750344128"))
    )
    (comp (ref "T4")
      (value "750344127")
      (fields (field (name "MANUFACTURER") "Wurth Electroniks"))
      (libsource (lib "eSpark Libraries") (part "750344127"))
    )
    (comp (ref "U5")
      (value "UCC24612-1DBVR")
      (footprint "SOT-23-5")
      (description "SYNC RECTIFIER FLYBACK")
      (fields (field (name "LCSC PART NUMBER") "C2657796") (field (name "MANUFACTURER") "Texas Instruments"))
      (libsource (lib "eSpark Libraries") (part "UCC24612-1DBVR"))
    )
    (comp (ref "U6")
      (value "LP2981-50DBVR")
      (footprint "SOT-23-5")
      (description "IC REG LINEAR 5V 100MA SOT23-5")
      (fields (field (name "LCSC PART NUMBER") "C2877856") (field (name "MANUFACTURER") "Texas Instruments"))
      (libsource (lib "eSpark Libraries") (part "LP2981-50DBVR"))
    )
    (comp (ref "U7")
      (value "UCC24612-1DBVR")
      (footprint "SOT-23-5")
      (description "SYNC RECTIFIER FLYBACK")
      (fields (field (name "LCSC PART NUMBER") "C2657796") (field (name "MANUFACTURER") "Texas Instruments"))
      (libsource (lib "eSpark Libraries") (part "UCC24612-1DBVR"))
    )
    (comp (ref "U8")
      (value "LP2951ACMX/NOPB")
      (footprint "SOIC-8")
      (description "IC REG LIN POS ADJ 100MA 8SOIC")
      (fields
        (field (name "LCSC PART NUMBER") "C67596")
        (field (name "MANUFACTURER") "TI National Semiconductor")
      )
      (libsource (lib "eSpark Libraries") (part "LP2951ACMX/NOPB"))
    )
    (comp (ref "U9")
      (value "UCC25630-1DDBR")
      (footprint "UCC25630-1DDBR")
      (description "Half-Bridge Regulator Positive, Isolation Capable Output DC-DC Controller IC 14-SOIC")
      (fields (field (name "MANUFACTURER") "Texas Instruments"))
      (libsource (lib "eSpark Libraries") (part "UCC25630-1DDBR"))
    )
    (comp (ref "U10")
      (value "VO618A-3X017T")
      (footprint "4-SMD  (SFH617A-1X007T)")
      (description "OPTOISOLATOR 5.3KV TRANS 4-SMD")
      (fields
        (field (name "LCSC PART NUMBER") "C143748")
        (field (name "MANUFACTURER") "Vishay Semiconductors")
      )
      (libsource (lib "eSpark Libraries") (part "VO618A-3X017T"))
    )
    (comp (ref "U11")
      (value "TL431ACDBZR")
      (footprint "SOT-23")
      (description "IC VREF SHUNT ADJ 1% SOT23-3")
      (fields (field (name "LCSC PART NUMBER") "C350683") (field (name "MANUFACTURER") "Texas Instruments"))
      (libsource (lib "eSpark Libraries") (part "TL431ACDBZR"))
    )
    (comp (ref "U12")
      (value "VO618A-3X017T")
      (footprint "4-SMD  (SFH617A-1X007T)")
      (description "OPTOISOLATOR 5.3KV TRANS 4-SMD")
      (fields
        (field (name "LCSC PART NUMBER") "C143748")
        (field (name "MANUFACTURER") "Vishay Semiconductors")
      )
      (libsource (lib "eSpark Libraries") (part "VO618A-3X017T"))
    )
    (comp (ref "U13")
      (value "INA181A4IDBVR")
      (footprint "SOT-23-6")
      (description "IC CURR SENSE 1 CIRCUIT SOT23-6")
      (fields (field (name "MANUFACTURER") "Texas Instruments"))
      (libsource (lib "eSpark Libraries") (part "INA181A4IDBVR"))
    )
    (comp (ref "U14")
      (value "TL331IDBVR")
      (footprint "SOT-23-5")
      (description "IC COMPARATOR 1 DIFF SOT23-5")
      (fields (field (name "LCSC PART NUMBER") "C80942") (field (name "MANUFACTURER") "Texas Instruments"))
      (libsource (lib "eSpark Libraries") (part "TL331IDBVR"))
    )
  )
  (nets
    (net (code "1") (name "+5V") (class "Default")
      (node (ref "C32") (pin "2") (pinfunction "2_2") (pintype "passive"))
      (node (ref "C67") (pin "2") (pinfunction "2_2") (pintype "passive"))
      (node (ref "R71") (pin "1") (pinfunction "1_1") (pintype "passive"))
      (node (ref "R74") (pin "2") (pinfunction "2_2") (pintype "passive"))
      (node (ref "U13") (pin "6") (pinfunction "VS_6") (pintype "passive"))
      (node (ref "U14") (pin "5") (pinfunction "VCC_5") (pintype "passive"))
      (node (ref "U6") (pin "5") (pinfunction "VOUT_5") (pintype "passive"))
    )
    (net (code "2") (name "+390V") (class "Default")
      (node (ref "C39") (pin "2") (pinfunction "2_2") (pintype "passive"))
      (node (ref "Q7") (pin "2") (pinfunction "D_2") (pintype "passive"))
      (node (ref "R55") (pin "2") (pinfunction "2_2") (pintype "passive"))
      (node (ref "T3") (pin "3") (pinfunction "3_3") (pintype "passive"))
    )
    (net (code "3") (name "/BLK") (class "Default")
      (node (ref "C66") (pin "2") (pinfunction "2_2") (pintype "passive"))
      (node (ref "R63") (pin "1") (pinfunction "1_1") (pintype "passive"))
      (node (ref "R67") (pin "2") (pinfunction "2_2") (pintype "passive"))
      (node (ref "U9") (pin "4") (pinfunction "BLK_4") (pintype "passive"))
    )
    (net (code "4") (name "/BW") (class "Default")
      (node (ref "C65") (pin "2") (pinfunction "2_2") (pintype "passive"))
      (node (ref "R46") (pin "1") (pinfunction "1_1") (pintype "passive"))
      (node (ref "R49") (pin "2") (pinfunction "2_2") (pintype "passive"))
      (node (ref "U9") (pin "8") (pinfunction "BW_8") (pintype "passive"))
    )
    (net (code "5") (name "/G1") (class "Default")
      (node (ref "R50") (pin "1") (pinfunction "1_1") (pintype "passive"))
      (node (ref "U5") (pin "1") (pinfunction "VG_1") (pintype "passive"))
    )
    (net (code "6") (name "/G2") (class "Default")
      (node (ref "R39") (pin "2") (pinfunction "2_2") (pintype "passive"))
      (node (ref "U7") (pin "1") (pinfunction "VG_1") (pintype "passive"))
    )
    (net (code "7") (name "/HO") (class "Default")
      (node (ref "D8") (pin "1") (pinfunction "A_1") (pintype "passive"))
      (node (ref "Q8") (pin "1") (pinfunction "B_1") (pintype "passive"))
      (node (ref "U9") (pin "15") (pinfunction "HO_15") (pintype "passive"))
    )
    (net (code "8") (name "/ISNS") (class "Default")
      (node (ref "C50") (pin "1") (pinfunction "1_1") (pintype "passive"))
      (node (ref "C53") (pin "2") (pinfunction "2_2") (pintype "passive"))
      (node (ref "R48") (pin "2") (pinfunction "2_2") (pintype "passive"))
      (node (ref "U9") (pin "6") (pinfunction "ISNS_6") (pintype "passive"))
    )
    (net (code "9") (name "/I_OUT") (class "Default")
      (node (ref "R73") (pin "1") (pinfunction "1_1") (pintype "passive"))
      (node (ref "U13") (pin "1") (pinfunction "OUT_1") (pintype "passive"))
    )
    (net (code "10") (name "/LL{slash}SS") (class "Default")
      (node (ref "C64") (pin "2") (pinfunction "2_2") (pintype "passive"))
      (node (ref "R59") (pin "1") (pinfunction "1_1") (pintype "passive"))
      (node (ref "R64") (pin "2") (pinfunction "2_2") (pintype "passive"))
      (node (ref "U12") (pin "4") (pinfunction "C_4") (pintype "passive"))
      (node (ref "U9") (pin "9") (pinfunction "LL_SS_9") (pintype "passive"))
    )
    (net (code "11") (name "/LO") (class "Default")
      (node (ref "D9") (pin "1") (pinfunction "A_1") (pintype "passive"))
      (node (ref "Q11") (pin "1") (pinfunction "B_1") (pintype "passive"))
      (node (ref "U9") (pin "10") (pinfunction "LO_10") (pintype "passive"))
    )
    (net (code "12") (name "/NET_A") (class "Default")
      (node (ref "R52") (pin "1") (pinfunction "1_1") (pintype "passive"))
    )
    (net (code "13") (name "/SW") (class "Default")
      (node (ref "C56") (pin "1") (pinfunction "1_1") (pintype "passive"))
      (node (ref "U9") (pin "16") (pinfunction "HS_16") (pintype "passive"))
    )
    (net (code "14") (name "/VCR") (class "Default")
      (node (ref "C49") (pin "1") (pinfunction "1_1") (pintype "passive"))
      (node (ref "C52") (pin "2") (pinfunction "2_2") (pintype "passive"))
      (node (ref "U9") (pin "7") (pinfunction "VCR_7") (pintype "passive"))
    )
    (net (code "15") (name "/VD1") (class "Default")
      (node (ref "Q10") (pin "5") (pinfunction "D_5") (pintype "passive"))
      (node (ref "Q10") (pin "6") (pinfunction "D_6") (pintype "passive"))
      (node (ref "Q10") (pin "7") (pinfunction "D_7") (pintype "passive"))
      (node (ref "Q10") (pin "8") (pinfunction "D_8") (pintype "passive"))
      (node (ref "R44") (pin "1") (pinfunction "1_1") (pintype "passive"))
      (node (ref "T4") (pin "10") (pinfunction "10_10") (pintype "passive"))
      (node (ref "U5") (pin "5") (pinfunction "VD_5") (pintype "passive"))
    )
    (net (code "16") (name "/VD2") (class "Default")
      (node (ref "Q6") (pin "5") (pinfunction "D_5") (pintype "passive"))
      (node (ref "Q6") (pin "6") (pinfunction "D_6") (pintype "passive"))
      (node (ref "Q6") (pin "7") (pinfunction "D_7") (pintype "passive"))
      (node (ref "Q6") (pin "8") (pinfunction "D_8") (pintype "passive"))
      (node (ref "R40") (pin "1") (pinfunction "1_1") (pintype "passive"))
      (node (ref "T4") (pin "7") (pinfunction "7_7") (pintype "passive"))
      (node (ref "U7") (pin "5") (pinfunction "VD_5") (pintype "passive"))
    )
    (net (code "17") (name "/X") (class "Default")
      (node (ref "D11") (pin "1") (pinfunction "A_1") (pintype "passive"))
      (node (ref "R46") (pin "2") (pinfunction "2_2") (pintype "passive"))
      (node (ref "T4") (pin "6") (pinfunction "6_6") (pintype "passive"))
    )
    (net (code "18") (name "12V") (class "Default")
      (node (ref "C60") (pin "2") (pinfunction "2_2") (pintype "passive"))
      (node (ref "C61") (pin "2") (pinfunction "2_2") (pintype "passive"))
      (node (ref "D10") (pin "2") (pinfunction "A_2") (pintype "passive"))
      (node (ref "R59") (pin "2") (pinfunction "2_2") (pintype "passive"))
      (node (ref "R65") (pin "1") (pinfunction "1_1") (pintype "passive"))
      (node (ref "U9") (pin "12") (pinfunction "RVCC_12") (pintype "passive"))
    )
    (net (code "19") (name "24V") (class "Default")
      (node (ref "C47") (pin "1") (pintype "passive"))
      (node (ref "L4") (pin "2") (pinfunction "2_2") (pintype "passive"))
      (node (ref "R57") (pin "1") (pinfunction "1_1") (pintype "passive"))
      (node (ref "R61") (pin "2") (pinfunction "2_2") (pintype "passive"))
    )
    (net (code "20") (name "AUX_15V") (class "Default")
      (node (ref "C54") (pin "2") (pinfunction "2_2") (pintype "passive"))
      (node (ref "R51") (pin "2") (pinfunction "2_2") (pintype "passive"))
      (node (ref "U8") (pin "1") (pinfunction "OUT_1") (pintype "passive"))
    )
    (net (code "21") (name "LDO_IN") (class "Default")
      (node (ref "C55") (pin "2") (pinfunction "2_2") (pintype "passive"))
      (node (ref "C57") (pin "1") (pinfunction "1_1") (pintype "passive"))
      (node (ref "C58") (pin "2") (pinfunction "2_2") (pintype "passive"))
      (node (ref "D11") (pin "2") (pinfunction "K_2") (pintype "passive"))
      (node (ref "U8") (pin "8") (pinfunction "IN_8") (pintype "passive"))
      (node (ref "U9") (pin "3") (pinfunction "VCC_3") (pintype "passive"))
    )
    (net (code "22") (name "Net-(C37-Pad1)") (class "Default")
      (node (ref "C37") (pin "1") (pinfunction "1_1") (pintype "passive"))
      (node (ref "R40") (pin "2") (pinfunction "2_2") (pintype "passive"))
    )
    (net (code "23") (name "Net-(C39-Pad1)") (class "Default")
      (node (ref "C39") (pin "1") (pinfunction "1_1") (pintype "passive"))
      (node (ref "C49") (pin "2") (pinfunction "2_2") (pintype "passive"))
      (node (ref "C50") (pin "2") (pinfunction "2_2") (pintype "passive"))
      (node (ref "C51") (pin "2") (pinfunction "2_2") (pintype "passive"))
      (node (ref "T4") (pin "3") (pinfunction "3_3") (pintype "passive"))
    )
    (net (code "24") (name "Net-(C48-Pad1)") (class "Default")
      (node (ref "C48") (pin "1") (pinfunction "1_1") (pintype "passive"))
      (node (ref "R44") (pin "2") (pinfunction "2_2") (pintype "passive"))
    )
    (net (code "25") (name "Net-(C59-Pad2)") (class "Default")
      (node (ref "C59") (pin "2") (pinfunction "2_2") (pintype "passive"))
      (node (ref "R62") (pin "2") (pinfunction "2_2") (pintype "passive"))
    )
    (net (code "26") (name "Net-(D8-K)") (class "Default")
      (node (ref "D8") (pin "2") (pinfunction "K_2") (pintype "passive"))
      (node (ref "R41") (pin "1") (pinfunction "1_1") (pintype "passive"))
    )
    (net (code "27") (name "Net-(D9-K)") (class "Default")
      (node (ref "D9") (pin "2") (pinfunction "K_2") (pintype "passive"))
      (node (ref "R45") (pin "1") (pinfunction "1_1") (pintype "passive"))
    )
    (net (code "28") (name "Net-(D10-K)") (class "Default")
      (node (ref "C56") (pin "2") (pinfunction "2_2") (pintype "passive"))
      (node (ref "D10") (pin "1") (pinfunction "K_1") (pintype "passive"))
      (node (ref "U9") (pin "14") (pinfunction "HB_14") (pintype "passive"))
    )
    (net (code "29") (name "Net-(Q4-B)") (class "Default")
      (node (ref "Q4") (pin "1") (pinfunction "B_1") (pintype "passive"))
      (node (ref "Q5") (pin "1") (pinfunction "K_1") (pintype "passive"))
      (node (ref "R38") (pin "1") (pinfunction "1_1") (pintype "passive"))
    )
    (net (code "30") (name "Net-(Q6-G)") (class "Default")
      (node (ref "Q6") (pin "4") (pinfunction "G_4") (pintype "passive"))
      (node (ref "R39") (pin "1") (pinfunction "1_1") (pintype "passive"))
    )
    (net (code "31") (name "Net-(Q7-G)") (class "Default")
      (node (ref "Q7") (pin "1") (pinfunction "G_1") (pintype "passive"))
      (node (ref "Q8") (pin "2") (pinfunction "E_2") (pintype "passive"))
      (node (ref "R41") (pin "2") (pinfunction "2_2") (pintype "passive"))
      (node (ref "R42") (pin "2") (pinfunction "2_2") (pintype "passive"))
    )
    (net (code "32") (name "Net-(Q7-S)") (class "Default")
      (node (ref "Q7") (pin "3") (pinfunction "S_3") (pintype "passive"))
      (node (ref "Q8") (pin "3") (pinfunction "C_3") (pintype "passive"))
      (node (ref "Q9") (pin "2") (pinfunction "D_2") (pintype "passive"))
      (node (ref "R42") (pin "1") (pinfunction "1_1") (pintype "passive"))
      (node (ref "T3") (pin "1") (pinfunction "1_1") (pintype "passive"))
    )
    (net (code "33") (name "Net-(Q10-G)") (class "Default")
      (node (ref "Q10") (pin "4") (pinfunction "G_4") (pintype "passive"))
      (node (ref "R50") (pin "2") (pinfunction "2_2") (pintype "passive"))
    )
    (net (code "34") (name "Net-(Q11-E)") (class "Default")
      (node (ref "Q11") (pin "2") (pinfunction "E_2") (pintype "passive"))
      (node (ref "Q9") (pin "1") (pinfunction "G_1") (pintype "passive"))
      (node (ref "R45") (pin "2") (pinfunction "2_2") (pintype "passive"))
      (node (ref "R47") (pin "2") (pinfunction "2_2") (pintype "passive"))
    )
    (net (code "35") (name "Net-(Q12-B)") (class "Default")
      (node (ref "Q12") (pin "1") (pinfunction "B_1") (pintype "passive"))
      (node (ref "R65") (pin "2") (pinfunction "2_2") (pintype "passive"))
      (node (ref "R68") (pin "2") (pinfunction "2_2") (pintype "passive"))
    )
    (net (code "36") (name "Net-(Q12-C)") (class "Default")
      (node (ref "Q12") (pin "3") (pinfunction "C_3") (pintype "passive"))
      (node (ref "U8") (pin "3") (pinfunction "SD_3") (pintype "passive"))
    )
    (net (code "37") (name "Net-(R52-Pad2)") (class "Default")
      (node (ref "R52") (pin "2") (pinfunction "2_2") (pintype "passive"))
      (node (ref "R53") (pin "1") (pinfunction "1_1") (pintype "passive"))
    )
    (net (code "38") (name "Net-(R53-Pad2)") (class "Default")
      (node (ref "R53") (pin "2") (pinfunction "2_2") (pintype "passive"))
      (node (ref "R54") (pin "1") (pinfunction "1_1") (pintype "passive"))
    )
    (net (code "39") (name "Net-(R55-Pad1)") (class "Default")
      (node (ref "R55") (pin "1") (pinfunction "1_1") (pintype "passive"))
      (node (ref "R58") (pin "2") (pinfunction "2_2") (pintype "passive"))
    )
    (net (code "40") (name "Net-(R58-Pad1)") (class "Default")
      (node (ref "R58") (pin "1") (pinfunction "1_1") (pintype "passive"))
      (node (ref "R63") (pin "2") (pinfunction "2_2") (pintype "passive"))
    )
    (net (code "41") (name "Net-(T3-Pad2)") (class "Default")
      (node (ref "T3") (pin "2") (pinfunction "2_2") (pintype "passive"))
      (node (ref "T4") (pin "1") (pinfunction "1_1") (pintype "passive"))
    )
    (net (code "42") (name "Net-(U5-REG)") (class "Default")
      (node (ref "C31") (pin "2") (pinfunction "2_2") (pintype "passive"))
      (node (ref "U5") (pin "3") (pinfunction "REG_3") (pintype "passive"))
    )
    (net (code "43") (name "Net-(U7-REG)") (class "Default")
      (node (ref "C35") (pin "2") (pinfunction "2_2") (pintype "passive"))
      (node (ref "U7") (pin "3") (pinfunction "REG_3") (pintype "passive"))
    )
    (net (code "44") (name "Net-(U8-FB)") (class "Default")
      (node (ref "R51") (pin "1") (pinfunction "1_1") (pintype "passive"))
      (node (ref "R56") (pin "2") (pinfunction "2_2") (pintype "passive"))
      (node (ref "U8") (pin "7") (pinfunction "FB_7") (pintype "passive"))
    )
    (net (code "45") (name "Net-(U9-HV)") (class "Default")
      (node (ref "R54") (pin "2") (pinfunction "2_2") (pintype "passive"))
      (node (ref "U9") (pin "1") (pinfunction "HV_1") (pintype "passive"))
    )
    (net (code "46") (name "Net-(U10-An)") (class "Default")
      (node (ref "R57") (pin "2") (pinfunction "2_2") (pintype "passive"))
      (node (ref "R60") (pin "2") (pinfunction "2_2") (pintype "passive"))
      (node (ref "U10") (pin "1") (pinfunction "An_1") (pintype "passive"))
    )
    (net (code "47") (name "Net-(U10-C)") (class "Default")
      (node (ref "C62") (pin "2") (pinfunction "2_2") (pintype "passive"))
      (node (ref "U10") (pin "4") (pinfunction "C_4") (pintype "passive"))
      (node (ref "U9") (pin "5") (pinfunction "FB_5") (pintype "passive"))
    )
    (net (code "48") (name "Net-(U10-Ca)") (class "Default")
      (node (ref "C59") (pin "1") (pinfunction "1_1") (pintype "passive"))
      (node (ref "C63") (pin "2") (pinfunction "2_2") (pintype "passive"))
      (node (ref "R60") (pin "1") (pinfunction "1_1") (pintype "passive"))
      (node (ref "U10") (pin "2") (pinfunction "Ca_2") (pintype "passive"))
      (node (ref "U11") (pin "1") (pinfunction "Cathode_1") (pintype "passive"))
    )
    (net (code "49") (name "Net-(U10-E)") (class "Default")
      (node (ref "R66") (pin "2") (pinfunction "2_2") (pintype "passive"))
      (node (ref "U10") (pin "3") (pinfunction "E_3") (pintype "passive"))
    )
    (net (code "50") (name "Net-(U11-REF)") (class "Default")
      (node (ref "C63") (pin "1") (pinfunction "1_1") (pintype "passive"))
      (node (ref "R61") (pin "1") (pinfunction "1_1") (pintype "passive"))
      (node (ref "R62") (pin "1") (pinfunction "1_1") (pintype "passive"))
      (node (ref "R69") (pin "2") (pinfunction "2_2") (pintype "passive"))
      (node (ref "U11") (pin "2") (pinfunction "REF_2") (pintype "passive"))
    )
    (net (code "51") (name "Net-(U12-An)") (class "Default")
      (node (ref "R71") (pin "2") (pinfunction "2_2") (pintype "passive"))
      (node (ref "R72") (pin "2") (pinfunction "2_2") (pintype "passive"))
      (node (ref "U12") (pin "1") (pinfunction "An_1") (pintype "passive"))
    )
    (net (code "52") (name "Net-(U12-Ca)") (class "Default")
      (node (ref "R70") (pin "2") (pinfunction "2_2") (pintype "passive"))
      (node (ref "R72") (pin "1") (pinfunction "1_1") (pintype "passive"))
      (node (ref "U12") (pin "2") (pinfunction "Ca_2") (pintype "passive"))
      (node (ref "U14") (pin "4") (pinfunction "OUT_4") (pintype "passive"))
    )
    (net (code "53") (name "Net-(U13-IN+)") (class "Default")
      (node (ref "R75") (pin "2") (pinfunction "2_2") (pintype "passive"))
      (node (ref "U13") (pin "3") (pinfunction "IN+_3") (pintype "passive"))
    )
    (net (code "54") (name "Net-(U13-IN-)") (class "Default")
      (node (ref "R76") (pin "2") (pinfunction "2_2") (pintype "passive"))
      (node (ref "U13") (pin "4") (pinfunction "IN-_4") (pintype "passive"))
    )
    (net (code "55") (name "Net-(U14-IN+)") (class "Default")
      (node (ref "R70") (pin "1") (pinfunction "1_1") (pintype "passive"))
      (node (ref "R74") (pin "1") (pinfunction "1_1") (pintype "passive"))
      (node (ref "R77") (pin "2") (pinfunction "2_2") (pintype "passive"))
      (node (ref "U14") (pin "3") (pinfunction "IN+_3") (pintype "passive"))
    )
    (net (code "56") (name "Net-(U14-IN-)") (class "Default")
      (node (ref "R73") (pin "2") (pinfunction "2_2") (pintype "passive"))
      (node (ref "U14") (pin "1") (pinfunction "IN-_1") (pintype "passive"))
    )
    (net (code "58") (name "PGND") (class "Default")
      (node (ref "C38") (pin "2") (pinfunction "2_2") (pintype "passive"))
      (node (ref "C51") (pin "1") (pinfunction "1_1") (pintype "passive"))
      (node (ref "C52") (pin "1") (pinfunction "1_1") (pintype "passive"))
      (node (ref "C53") (pin "1") (pinfunction "1_1") (pintype "passive"))
      (node (ref "C54") (pin "1") (pinfunction "1_1") (pintype "passive"))
      (node (ref "C55") (pin "1") (pinfunction "1_1") (pintype "passive"))
      (node (ref "C57") (pin "2") (pinfunction "2_2") (pintype "passive"))
      (node (ref "C58") (pin "1") (pinfunction "1_1") (pintype "passive"))
      (node (ref "C60") (pin "1") (pinfunction "1_1") (pintype "passive"))
      (node (ref "C61") (pin "1") (pinfunction "1_1") (pintype "passive"))
      (node (ref "C62") (pin "1") (pinfunction "1_1") (pintype "passive"))
      (node (ref "C64") (pin "1") (pinfunction "1_1") (pintype "passive"))
      (node (ref "C65") (pin "1") (pinfunction "1_1") (pintype "passive"))
      (node (ref "C66") (pin "1") (pinfunction "1_1") (pintype "passive"))
      (node (ref "Q11") (pin "3") (pinfunction "C_3") (pintype "passive"))
      (node (ref "Q12") (pin "2") (pinfunction "E_2") (pintype "passive"))
      (node (ref "Q9") (pin "3") (pinfunction "S_3") (pintype "passive"))
      (node (ref "R47") (pin "1") (pinfunction "1_1") (pintype "passive"))
      (node (ref "R48") (pin "1") (pinfunction "1_1") (pintype "passive"))
      (node (ref "R49") (pin "1") (pinfunction "1_1") (pintype "passive"))
      (node (ref "R56") (pin "1") (pinfunction "1_1") (pintype "passive"))
      (node (ref "R64") (pin "1") (pinfunction "1_1") (pintype "passive"))
      (node (ref "R66") (pin "1") (pinfunction "1_1") (pintype "passive"))
      (node (ref "R67") (pin "1") (pinfunction "1_1") (pintype "passive"))
      (node (ref "R68") (pin "1") (pinfunction "1_1") (pintype "passive"))
      (node (ref "T4") (pin "5") (pinfunction "5_5") (pintype "passive"))
      (node (ref "U12") (pin "3") (pinfunction "E_3") (pintype "passive"))
      (node (ref "U8") (pin "4") (pinfunction "GND_4") (pintype "passive"))
      (node (ref "U9") (pin "11") (pinfunction "GND_11") (pintype "passive"))
    )
    (net (code "59") (name "R_SENSE") (class "Default")
      (node (ref "R43") (pin "2") (pinfunction "2_2") (pintype "passive"))
      (node (ref "R75") (pin "1") (pinfunction "1_1") (pintype "passive"))
    )
    (net (code "60") (name "SGND") (class "Default")
      (node (ref "C30") (pin "1") (pinfunction "1_1") (pintype "passive"))
      (node (ref "C31") (pin "1") (pinfunction "1_1") (pintype "passive"))
      (node (ref "C32") (pin "1") (pinfunction "1_1") (pintype "passive"))
      (node (ref "C33") (pin "1") (pinfunction "1_1") (pintype "passive"))
      (node (ref "C34") (pin "1") (pinfunction "1_1") (pintype "passive"))
      (node (ref "C35") (pin "1") (pinfunction "1_1") (pintype "passive"))
      (node (ref "C37") (pin "2") (pinfunction "2_2") (pintype "passive"))
      (node (ref "C40") (pin "1") (pinfunction "1_1") (pintype "passive"))
      (node (ref "C41") (pin "1") (pinfunction "1_1") (pintype "passive"))
      (node (ref "C42") (pin "1") (pinfunction "1_1") (pintype "passive"))
      (node (ref "C43") (pin "1") (pinfunction "1_1") (pintype "passive"))
      (node (ref "C44") (pin "2") (pintype "passive"))
      (node (ref "C45") (pin "2") (pintype "passive"))
      (node (ref "C46") (pin "2") (pintype "passive"))
      (node (ref "C47") (pin "2") (pintype "passive"))
      (node (ref "C48") (pin "2") (pinfunction "2_2") (pintype "passive"))
      (node (ref "C67") (pin "1") (pinfunction "1_1") (pintype "passive"))
      (node (ref "Q10") (pin "1") (pinfunction "S_1") (pintype "passive"))
      (node (ref "Q10") (pin "2") (pinfunction "S_2") (pintype "passive"))
      (node (ref "Q10") (pin "3") (pinfunction "S_3") (pintype "passive"))
      (node (ref "Q5") (pin "2") (pinfunction "A_2") (pintype "passive"))
      (node (ref "Q6") (pin "1") (pinfunction "S_1") (pintype "passive"))
      (node (ref "Q6") (pin "2") (pinfunction "S_2") (pintype "passive"))
      (node (ref "Q6") (pin "3") (pinfunction "S_3") (pintype "passive"))
      (node (ref "R43") (pin "1") (pinfunction "1_1") (pintype "passive"))
      (node (ref "R69") (pin "1") (pinfunction "1_1") (pintype "passive"))
      (node (ref "R76") (pin "1") (pinfunction "1_1") (pintype "passive"))
      (node (ref "R77") (pin "1") (pinfunction "1_1") (pintype "passive"))
      (node (ref "U11") (pin "3") (pinfunction "Anode_3") (pintype "passive"))
      (node (ref "U13") (pin "2") (pinfunction "GND_2") (pintype "passive"))
      (node (ref "U13") (pin "5") (pinfunction "REF_5") (pintype "passive"))
      (node (ref "U14") (pin "2") (pinfunction "VCC-/GND_2") (pintype "passive"))
      (node (ref "U5") (pin "2") (pinfunction "VS_2") (pintype "passive"))
      (node (ref "U6") (pin "2") (pinfunction "GND_2") (pintype "passive"))
      (node (ref "U7") (pin "2") (pinfunction "VS_2") (pintype "passive"))
    )
    (net (code "61") (name "V24V") (class "Default")
      (node (ref "C38") (pin "1") (pinfunction "1_1") (pintype "passive"))
      (node (ref "C40") (pin "2") (pinfunction "2_2") (pintype "passive"))
      (node (ref "C41") (pin "2") (pinfunction "2_2") (pintype "passive"))
      (node (ref "C42") (pin "2") (pinfunction "2_2") (pintype "passive"))
      (node (ref "C43") (pin "2") (pinfunction "2_2") (pintype "passive"))
      (node (ref "C44") (pin "1") (pintype "passive"))
      (node (ref "C45") (pin "1") (pintype "passive"))
      (node (ref "C46") (pin "1") (pintype "passive"))
      (node (ref "L4") (pin "1") (pinfunction "1_1") (pintype "passive"))
      (node (ref "Q4") (pin "3") (pinfunction "C_3") (pintype "passive"))
      (node (ref "R38") (pin "2") (pinfunction "2_2") (pintype "passive"))
      (node (ref "T4") (pin "8") (pinfunction "8_8") (pintype "passive"))
      (node (ref "T4") (pin "9") (pinfunction "9_9") (pintype "passive"))
    )
    (net (code "62") (name "VDD") (class "Default")
      (node (ref "C30") (pin "2") (pinfunction "2_2") (pintype "passive"))
      (node (ref "C33") (pin "2") (pinfunction "2_2") (pintype "passive"))
      (node (ref "C34") (pin "2") (pinfunction "2_2") (pintype "passive"))
      (node (ref "Q4") (pin "2") (pinfunction "E_2") (pintype "passive"))
      (node (ref "U5") (pin "4") (pinfunction "VDD_4") (pintype "passive"))
      (node (ref "U6") (pin "1") (pinfunction "VIN_1") (pintype "passive"))
      (node (ref "U6") (pin "3") (pinfunction "ON/OFF_3") (pintype "passive"))
      (node (ref "U7") (pin "4") (pinfunction "VDD_4") (pintype "passive"))
    )
    (net (code "63") (name "unconnected-(T3-Pad4)") (class "Default")
      (node (ref "T3") (pin "4") (pintype "passive+no_connect"))
    )
    (net (code "64") (name "unconnected-(T4-Pad2)") (class "Default")
      (node (ref "T4") (pin "2") (pinfunction "2_2") (pintype "passive+no_connect"))
    )
    (net (code "65") (name "unconnected-(T4-Pad4)") (class "Default")
      (node (ref "T4") (pin "4") (pinfunction "4_4") (pintype "passive+no_connect"))
    )
    (net (code "66") (name "unconnected-(U6-NC-Pad4)") (class "Default")
      (node (ref "U6") (pin "4") (pinfunction "NC_4") (pintype "passive+no_connect"))
    )
    (net (code "67") (name "unconnected-(U8-ERROR#-Pad5)") (class "Default")
      (node (ref "U8") (pin "5") (pinfunction "ERROR#_5") (pintype "passive+no_connect"))
    )
    (net (code "68") (name "unconnected-(U8-SNS-Pad2)") (class "Default")
      (node (ref "U8") (pin "2") (pinfunction "SNS_2") (pintype "passive+no_connect"))
    )
    (net (code "69") (name "unconnected-(U8-VTAP-Pad6)") (class "Default")
      (node (ref "U8") (pin "6") (pinfunction "VTAP_6") (pintype "passive+no_connect"))
    )
  )
)
